# Data_Over_Power_Breakout.net
KiCad netlist of a schematic drawn in EAGLE
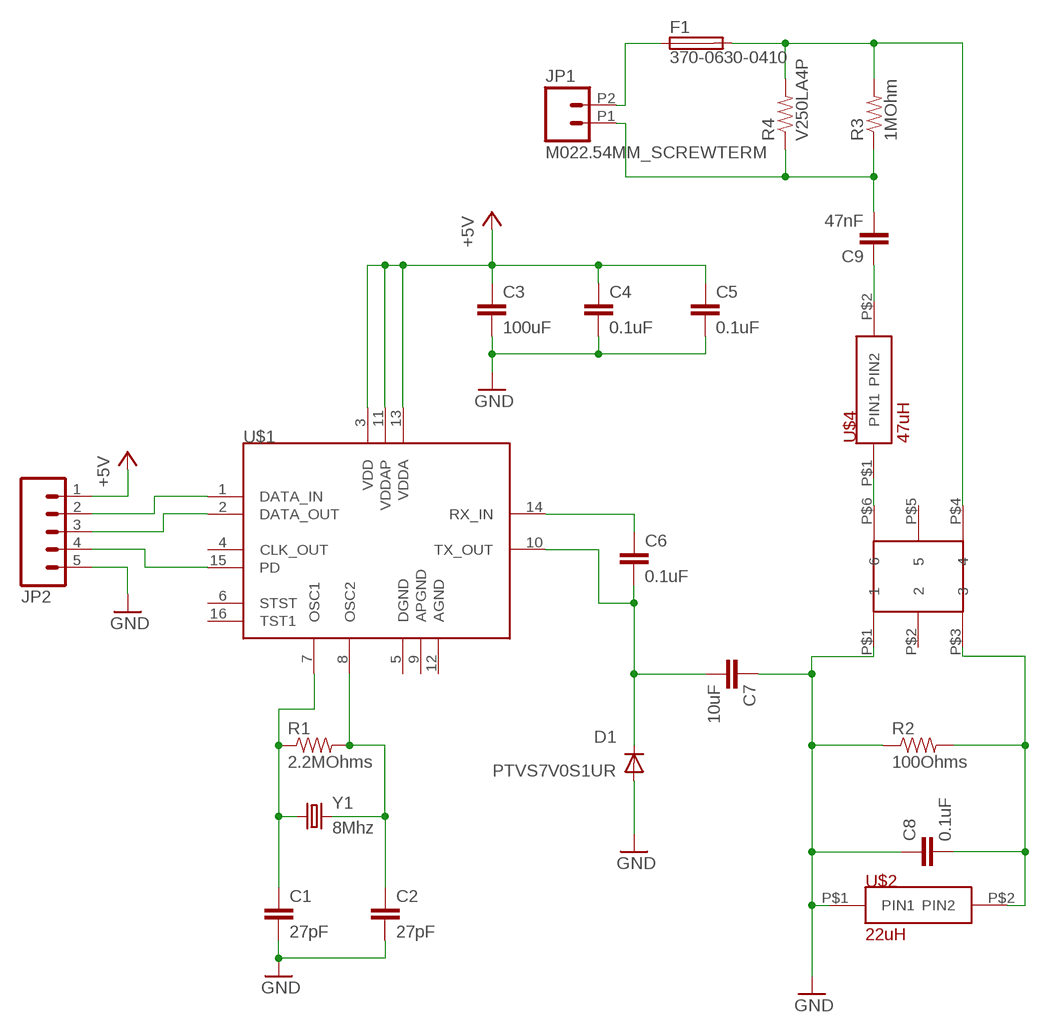
[diagram p0: schematic, sheet 1]

(export (version "E")
  (design (tool "Eeschema 10.0.6"))
  (components
    (comp (ref "C1")
      (value "27pF")
      (footprint "eagle-import:1206")
      (libsource (lib "eagle-import") (part "SparkFun-Passives_CAP1206"))
    )
    (comp (ref "C2")
      (value "27pF")
      (footprint "eagle-import:1206")
      (libsource (lib "eagle-import") (part "SparkFun-Passives_CAP1206"))
    )
    (comp (ref "C3")
      (value "100uF")
      (footprint "eagle-import:1206")
      (libsource (lib "eagle-import") (part "SparkFun-Passives_CAP1206"))
    )
    (comp (ref "C4")
      (value "0.1uF")
      (footprint "eagle-import:1206")
      (libsource (lib "eagle-import") (part "SparkFun-Passives_CAP1206"))
    )
    (comp (ref "C5")
      (value "0.1uF")
      (footprint "eagle-import:1206")
      (libsource (lib "eagle-import") (part "SparkFun-Passives_CAP1206"))
    )
    (comp (ref "C6")
      (value "0.1uF")
      (footprint "eagle-import:AXIAL-5MM")
      (libsource (lib "eagle-import") (part "SparkFun-Passives_CAP_"))
    )
    (comp (ref "C7")
      (value "10uF")
      (footprint "eagle-import:CAP-PTH-SMALL")
      (libsource (lib "eagle-import") (part "CAPPTH"))
    )
    (comp (ref "C8")
      (value "0.1uF")
      (footprint "eagle-import:1206")
      (libsource (lib "eagle-import") (part "SparkFun-Passives_CAP1206"))
    )
    (comp (ref "C9")
      (value "47nF")
      (footprint "eagle-import:C15B5")
      (libsource (lib "eagle-import") (part "C15/5"))
    )
    (comp (ref "D1")
      (value "PTVS7V0S1UR")
      (footprint "eagle-import:SOD-123_MINI-SMA")
      (libsource (lib "eagle-import") (part "CGRM400-G1"))
    )
    (comp (ref "F1")
      (value "370-0630-0410")
      (footprint "eagle-import:TR5")
      (libsource (lib "eagle-import") (part "TR5"))
    )
    (comp (ref "JP1")
      (value "M022.54MM_SCREWTERM")
      (footprint "eagle-import:1X02_2.54_SCREWTERM")
      (libsource (lib "eagle-import") (part "M022.54MM_SCREWTERM"))
    )
    (comp (ref "JP2")
      (value "M05PTH_LONGPADS")
      (footprint "eagle-import:1X05_LONGPADS")
      (libsource (lib "eagle-import") (part "M05PTH_LONGPADS"))
    )
    (comp (ref "R1")
      (value "2.2MOhms")
      (footprint "eagle-import:1206")
      (libsource (lib "eagle-import") (part "RESISTOR1206"))
    )
    (comp (ref "R2")
      (value "100Ohms")
      (footprint "eagle-import:AXIAL-0.5")
      (libsource (lib "eagle-import") (part "SparkFun-Resistors_RESISTORPTH-1/2W"))
    )
    (comp (ref "R3")
      (value "1MOhm")
      (footprint "eagle-import:AXIAL-0.3-KIT")
      (libsource (lib "eagle-import") (part "10KOHM1/6W5%(PTH)KIT"))
    )
    (comp (ref "R4")
      (value "V250LA4P")
      (footprint "eagle-import:AXIAL-0.4")
      (libsource (lib "eagle-import") (part "RESISTORPTH-1/4W"))
    )
    (comp (ref "U$1")
      (value "TDA5052AT")
      (footprint "eagle-import:SO16L")
      (libsource (lib "eagle-import") (part "TDA5052AT"))
    )
    (comp (ref "U$2")
      (value "22uH")
      (footprint "eagle-import:RFB0807-220L")
      (libsource (lib "eagle-import") (part "RFB0807-220L"))
    )
    (comp (ref "U$3")
      (value "78250MC")
      (footprint "eagle-import:78250MC")
      (libsource (lib "eagle-import") (part "78250MC"))
    )
    (comp (ref "U$4")
      (value "47uH")
      (footprint "eagle-import:RFB0807-220L")
      (libsource (lib "eagle-import") (part "RFB0807-220L"))
    )
    (comp (ref "Y1")
      (value "8Mhz")
      (footprint "eagle-import:HC49US")
      (libsource (lib "eagle-import") (part "CRYSTALHC49US"))
    )
  )
  (nets
    (net (code "1") (name "+5V") (class "Default")
      (node (ref "C3") (pin "1") (pinfunction "1_1") (pintype "passive"))
      (node (ref "C4") (pin "1") (pinfunction "1_1") (pintype "passive"))
      (node (ref "C5") (pin "1") (pinfunction "1_1") (pintype "passive"))
      (node (ref "JP2") (pin "1") (pinfunction "1_1") (pintype "passive"))
      (node (ref "U$1") (pin "11") (pinfunction "VDDAP_11") (pintype "bidirectional"))
      (node (ref "U$1") (pin "13") (pinfunction "VDDA_13") (pintype "bidirectional"))
      (node (ref "U$1") (pin "3") (pinfunction "VDD_3") (pintype "bidirectional"))
    )
    (net (code "2") (name "GND") (class "Default")
      (node (ref "C1") (pin "2") (pinfunction "2_2") (pintype "passive"))
      (node (ref "C2") (pin "2") (pinfunction "2_2") (pintype "passive"))
      (node (ref "C3") (pin "2") (pinfunction "2_2") (pintype "passive"))
      (node (ref "C4") (pin "2") (pinfunction "2_2") (pintype "passive"))
      (node (ref "C5") (pin "2") (pinfunction "2_2") (pintype "passive"))
      (node (ref "C7") (pin "1") (pinfunction "1_1") (pintype "passive"))
      (node (ref "C8") (pin "1") (pinfunction "1_1") (pintype "passive"))
      (node (ref "D1") (pin "A") (pinfunction "A_A") (pintype "passive"))
      (node (ref "JP2") (pin "5") (pinfunction "5_5") (pintype "passive"))
      (node (ref "R2") (pin "P$1") (pinfunction "1_P$1") (pintype "passive"))
      (node (ref "U$2") (pin "P$1") (pinfunction "PIN1_P$1") (pintype "bidirectional"))
      (node (ref "U$3") (pin "P$1") (pinfunction "1_P$1") (pintype "bidirectional"))
    )
    (net (code "3") (name "Net-(C6-1)") (class "Default")
      (node (ref "C6") (pin "P$1") (pinfunction "1_P$1") (pintype "passive"))
      (node (ref "U$1") (pin "14") (pinfunction "RX_IN_14") (pintype "bidirectional"))
    )
    (net (code "4") (name "Net-(C6-2)") (class "Default")
      (node (ref "C6") (pin "P$2") (pinfunction "2_P$2") (pintype "passive"))
      (node (ref "C7") (pin "2") (pinfunction "2_2") (pintype "passive"))
      (node (ref "D1") (pin "C") (pinfunction "C_C") (pintype "passive"))
      (node (ref "U$1") (pin "10") (pinfunction "TX_OUT_10") (pintype "bidirectional"))
    )
    (net (code "5") (name "Net-(JP1-1)") (class "Default")
      (node (ref "C9") (pin "2") (pinfunction "2_2") (pintype "passive"))
      (node (ref "JP1") (pin "P1") (pinfunction "1_P1") (pintype "passive"))
      (node (ref "R3") (pin "P$1") (pinfunction "1_P$1") (pintype "passive"))
      (node (ref "R4") (pin "P$1") (pinfunction "1_P$1") (pintype "passive"))
    )
    (net (code "6") (name "Net-(JP1-2)") (class "Default")
      (node (ref "F1") (pin "1") (pinfunction "1_1") (pintype "passive"))
      (node (ref "JP1") (pin "P2") (pinfunction "2_P2") (pintype "passive"))
    )
    (net (code "7") (name "Net-(R2-2)") (class "Default")
      (node (ref "C8") (pin "2") (pinfunction "2_2") (pintype "passive"))
      (node (ref "R2") (pin "P$2") (pinfunction "2_P$2") (pintype "passive"))
      (node (ref "U$2") (pin "P$2") (pinfunction "PIN2_P$2") (pintype "bidirectional"))
      (node (ref "U$3") (pin "P$3") (pinfunction "3_P$3") (pintype "bidirectional"))
    )
    (net (code "8") (name "Net-(R3-2)") (class "Default")
      (node (ref "F1") (pin "2") (pinfunction "2_2") (pintype "passive"))
      (node (ref "R3") (pin "P$2") (pinfunction "2_P$2") (pintype "passive"))
      (node (ref "R4") (pin "P$2") (pinfunction "2_P$2") (pintype "passive"))
      (node (ref "U$3") (pin "P$4") (pinfunction "4_P$4") (pintype "bidirectional"))
    )
    (net (code "9") (name "Net-(U$1-DATA_IN)") (class "Default")
      (node (ref "JP2") (pin "2") (pinfunction "2_2") (pintype "passive"))
      (node (ref "U$1") (pin "1") (pinfunction "DATA_IN_1") (pintype "bidirectional"))
    )
    (net (code "10") (name "Net-(U$1-DATA_OUT)") (class "Default")
      (node (ref "JP2") (pin "3") (pinfunction "3_3") (pintype "passive"))
      (node (ref "U$1") (pin "2") (pinfunction "DATA_OUT_2") (pintype "bidirectional"))
    )
    (net (code "11") (name "Net-(U$1-OSC1)") (class "Default")
      (node (ref "C1") (pin "1") (pinfunction "1_1") (pintype "passive"))
      (node (ref "R1") (pin "1") (pinfunction "1_1") (pintype "passive"))
      (node (ref "U$1") (pin "7") (pinfunction "OSC1_7") (pintype "bidirectional"))
      (node (ref "Y1") (pin "1") (pinfunction "1_1") (pintype "passive"))
    )
    (net (code "12") (name "Net-(U$1-OSC2)") (class "Default")
      (node (ref "C2") (pin "1") (pinfunction "1_1") (pintype "passive"))
      (node (ref "R1") (pin "2") (pinfunction "2_2") (pintype "passive"))
      (node (ref "U$1") (pin "8") (pinfunction "OSC2_8") (pintype "bidirectional"))
      (node (ref "Y1") (pin "2") (pinfunction "2_2") (pintype "passive"))
    )
    (net (code "13") (name "Net-(U$1-PD)") (class "Default")
      (node (ref "JP2") (pin "4") (pinfunction "4_4") (pintype "passive"))
      (node (ref "U$1") (pin "15") (pinfunction "PD_15") (pintype "bidirectional"))
    )
    (net (code "14") (name "Net-(U$3-6)") (class "Default")
      (node (ref "U$3") (pin "P$6") (pinfunction "6_P$6") (pintype "bidirectional"))
      (node (ref "U$4") (pin "P$1") (pinfunction "PIN1_P$1") (pintype "bidirectional"))
    )
    (net (code "15") (name "Net-(U$4-PIN2)") (class "Default")
      (node (ref "C9") (pin "1") (pinfunction "1_1") (pintype "passive"))
      (node (ref "U$4") (pin "P$2") (pinfunction "PIN2_P$2") (pintype "bidirectional"))
    )
    (net (code "16") (name "unconnected-(U$1-AGND-Pad12)") (class "Default")
      (node (ref "U$1") (pin "12") (pinfunction "AGND_12") (pintype "bidirectional"))
    )
    (net (code "17") (name "unconnected-(U$1-APGND-Pad9)") (class "Default")
      (node (ref "U$1") (pin "9") (pinfunction "APGND_9") (pintype "bidirectional"))
    )
    (net (code "18") (name "unconnected-(U$1-CLK_OUT-Pad4)") (class "Default")
      (node (ref "U$1") (pin "4") (pinfunction "CLK_OUT_4") (pintype "bidirectional"))
    )
    (net (code "19") (name "unconnected-(U$1-DGND-Pad5)") (class "Default")
      (node (ref "U$1") (pin "5") (pinfunction "DGND_5") (pintype "bidirectional"))
    )
    (net (code "20") (name "unconnected-(U$1-STST-Pad6)") (class "Default")
      (node (ref "U$1") (pin "6") (pinfunction "STST_6") (pintype "bidirectional"))
    )
    (net (code "21") (name "unconnected-(U$1-TST1-Pad16)") (class "Default")
      (node (ref "U$1") (pin "16") (pinfunction "TST1_16") (pintype "bidirectional"))
    )
    (net (code "22") (name "unconnected-(U$3-2-PadP$2)") (class "Default")
      (node (ref "U$3") (pin "P$2") (pinfunction "2_P$2") (pintype "bidirectional"))
    )
    (net (code "23") (name "unconnected-(U$3-5-PadP$5)") (class "Default")
      (node (ref "U$3") (pin "P$5") (pinfunction "5_P$5") (pintype "bidirectional"))
    )
  )
)
